# v1_0.net
KiCad netlist of a schematic drawn in Altium Designer
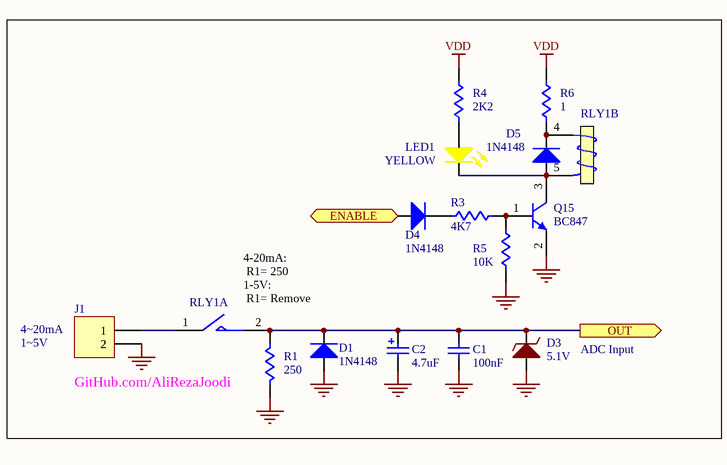
[diagram p0: v1.0.SchDoc]

(export (version "E")
  (design (tool "Eeschema 10.0.6"))
  (components
    (comp (ref "C1")
      (value "100nF")
      (footprint "CAPNTO2.54-3.05x1.78A")
      (description "Capacitor")
      (fields (field (name "MANUFACTURER") "Generic Components") (field (name "PUBLISHER") "Altium Limited"))
      (libsource (lib "Miscellaneous Devices") (part "Cap"))
    )
    (comp (ref "C2")
      (value "4.7uF")
      (footprint "CAPPR2.5-6.3x5")
      (description "Polarized Capacitor (Radial)")
      (fields (field (name "MANUFACTURER") "Generic Components") (field (name "PUBLISHER") "Altium Limited"))
      (libsource (lib "Miscellaneous Devices") (part "Cap Pol1"))
    )
    (comp (ref "D1")
      (value "1N4148")
      (footprint "D_THD_AXIAL0.4_DO-41")
      (description "Diode,")
      (libsource (lib "Passive") (part "Diode"))
    )
    (comp (ref "D3")
      (value "5.1V")
      (footprint "D_THD_AXIAL0.3_DO-35")
      (description "Diode, Zener")
      (libsource (lib "Passive") (part "Diode_Zener"))
    )
    (comp (ref "D4")
      (value "1N4148")
      (footprint "0805_Diode")
      (description "Default Diode")
      (fields
        (field (name "MANUFACTURER") "Generic Components")
        (field (name "Comment") "Diode")
        (field (name "PUBLISHER") "Altium Limited")
      )
      (libsource (lib "Miscellaneous Devices") (part "Diode"))
    )
    (comp (ref "D5")
      (value "1N4148")
      (footprint "0805_Diode")
      (description "Default Diode")
      (fields
        (field (name "MANUFACTURER") "Generic Components")
        (field (name "Comment") "Diode")
        (field (name "PUBLISHER") "Altium Limited")
      )
      (libsource (lib "Miscellaneous Devices") (part "Diode"))
    )
    (comp (ref "J1")
      (value "Header 2")
      (footprint "Fonics_2PIN_1")
      (description "Header, 2-Pin")
      (fields (field (name "PUBLISHER") "Altium Limited"))
      (libsource (lib "Miscellaneous Connectors") (part "Header 2"))
    )
    (comp (ref "LED1")
      (value "YELLOW")
      (footprint "LED_THD_3MM_YELLOW_R")
      (description "LED, Yellow")
      (fields (field (name "MANUFACTURER") "Generic Components") (field (name "PUBLISHER") "Altium Limited"))
      (libsource (lib "Display") (part "LED_YELLOW"))
    )
    (comp (ref "Q1")
      (value "Q15")
      (footprint "SOT23-3N")
      (description "Silicon Bipolar Transistor")
      (fields (field (name "ALTIUM_VALUE") "BC847"))
      (libsource (lib "my Libraries") (part "BC847"))
    )
    (comp (ref "R1")
      (value "250")
      (footprint "AXIAL-0.4")
      (description "Resistor")
      (fields (field (name "MANUFACTURER") "Generic Components") (field (name "PUBLISHER") "Altium Limited"))
      (libsource (lib "Miscellaneous Devices") (part "Res1"))
    )
    (comp (ref "R3")
      (value "4K7")
      (footprint "0805")
      (description "Resistor")
      (fields
        (field (name "MANUFACTURER") "Generic Components")
        (field (name "Comment") "Res1")
        (field (name "PUBLISHER") "Altium Limited")
      )
      (libsource (lib "Miscellaneous Devices") (part "Res1"))
    )
    (comp (ref "R4")
      (value "2K2")
      (footprint "0805")
      (description "Resistor")
      (fields
        (field (name "MANUFACTURER") "Generic Components")
        (field (name "Comment") "Res1")
        (field (name "PUBLISHER") "Altium Limited")
      )
      (libsource (lib "Miscellaneous Devices") (part "Res1"))
    )
    (comp (ref "R5")
      (value "10K")
      (footprint "0805")
      (description "Resistor")
      (fields
        (field (name "MANUFACTURER") "Generic Components")
        (field (name "Comment") "Res1")
        (field (name "PUBLISHER") "Altium Limited")
      )
      (libsource (lib "Miscellaneous Devices") (part "Res1"))
    )
    (comp (ref "R6")
      (value "1")
      (footprint "RESC3216N")
      (description "Resistor")
      (fields (field (name "MANUFACTURER") "Generic Components") (field (name "PUBLISHER") "Altium Limited"))
      (libsource (lib "Miscellaneous Devices") (part "Res1"))
    )
    (comp (ref "RLY1")
      (value "RELAU")
      (footprint "RELAY-SPDT-2")
      (fields (field (name "PUBLISHER") "Altium Limited"))
      (libsource (lib "my Libraries") (part "RELAY-NY12W-K"))
    )
  )
  (nets
    (net (code "1") (name "/ENABLE") (class "Default")
      (node (ref "D4") (pin "1") (pinfunction "A_1") (pintype "passive"))
    )
    (net (code "2") (name "/OUT") (class "Default")
      (node (ref "C1") (pin "2") (pinfunction "2_2") (pintype "passive"))
      (node (ref "C2") (pin "1") (pinfunction "1_1") (pintype "passive"))
      (node (ref "D1") (pin "2") (pinfunction "K_2") (pintype "passive"))
      (node (ref "D3") (pin "2") (pinfunction "2_2") (pintype "passive"))
      (node (ref "R1") (pin "1") (pinfunction "1_1") (pintype "passive"))
      (node (ref "RLY1") (pin "2") (pinfunction "NO_2") (pintype "passive"))
    )
    (net (code "3") (name "GND") (class "Default")
      (node (ref "C1") (pin "1") (pinfunction "1_1") (pintype "passive"))
      (node (ref "C2") (pin "2") (pinfunction "2_2") (pintype "passive"))
      (node (ref "D1") (pin "1") (pinfunction "A_1") (pintype "passive"))
      (node (ref "D3") (pin "1") (pinfunction "1_1") (pintype "passive"))
      (node (ref "J1") (pin "2") (pinfunction "2_2") (pintype "passive"))
      (node (ref "Q1") (pin "2") (pinfunction "E_2") (pintype "passive"))
      (node (ref "R1") (pin "2") (pinfunction "2_2") (pintype "passive"))
      (node (ref "R5") (pin "1") (pinfunction "1_1") (pintype "passive"))
    )
    (net (code "4") (name "Net-(D4-K)") (class "Default")
      (node (ref "D4") (pin "2") (pinfunction "K_2") (pintype "passive"))
      (node (ref "R3") (pin "1") (pinfunction "1_1") (pintype "passive"))
    )
    (net (code "5") (name "Net-(D5-A)") (class "Default")
      (node (ref "D5") (pin "1") (pinfunction "A_1") (pintype "passive"))
      (node (ref "LED1") (pin "2") (pinfunction "K_2") (pintype "passive"))
      (node (ref "Q1") (pin "3") (pinfunction "C_3") (pintype "passive"))
      (node (ref "RLY1") (pin "5") (pinfunction "T2_5") (pintype "passive"))
    )
    (net (code "6") (name "Net-(D5-K)") (class "Default")
      (node (ref "D5") (pin "2") (pinfunction "K_2") (pintype "passive"))
      (node (ref "R6") (pin "2") (pinfunction "2_2") (pintype "passive"))
      (node (ref "RLY1") (pin "4") (pinfunction "T1_4") (pintype "passive"))
    )
    (net (code "7") (name "Net-(LED1-A)") (class "Default")
      (node (ref "LED1") (pin "1") (pinfunction "A_1") (pintype "passive"))
      (node (ref "R4") (pin "2") (pinfunction "2_2") (pintype "passive"))
    )
    (net (code "8") (name "Net-(Q1-B)") (class "Default")
      (node (ref "Q1") (pin "1") (pinfunction "B_1") (pintype "passive"))
      (node (ref "R3") (pin "2") (pinfunction "2_2") (pintype "passive"))
      (node (ref "R5") (pin "2") (pinfunction "2_2") (pintype "passive"))
    )
    (net (code "9") (name "Net-(RLY1A-COM)") (class "Default")
      (node (ref "J1") (pin "1") (pinfunction "1_1") (pintype "passive"))
      (node (ref "RLY1") (pin "1") (pinfunction "COM_1") (pintype "passive"))
    )
    (net (code "10") (name "VDD") (class "Default")
      (node (ref "R4") (pin "1") (pinfunction "1_1") (pintype "passive"))
      (node (ref "R6") (pin "1") (pinfunction "1_1") (pintype "passive"))
    )
  )
)
